# main.net
KiCad netlist of a schematic drawn in EAGLE
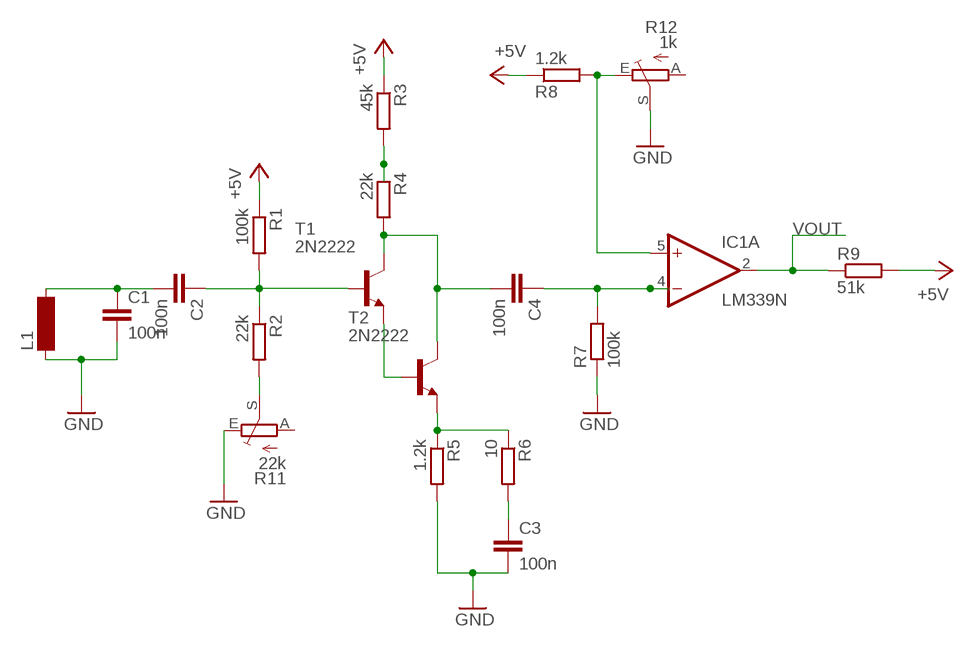
[diagram p0: schematic, sheet 1]

(export (version "E")
  (design (tool "Eeschema 10.0.6"))
  (components
    (comp (ref "C1")
      (value "100n")
      (footprint "eagle-import:C025-024X044")
      (libsource (lib "eagle-import") (part "C-EU025-024X044"))
    )
    (comp (ref "C2")
      (value "100n")
      (footprint "eagle-import:C025-024X044")
      (libsource (lib "eagle-import") (part "C-EU025-024X044"))
    )
    (comp (ref "C3")
      (value "100n")
      (footprint "eagle-import:C025-024X044")
      (libsource (lib "eagle-import") (part "C-EU025-024X044"))
    )
    (comp (ref "C4")
      (value "100n")
      (footprint "eagle-import:C025-024X044")
      (libsource (lib "eagle-import") (part "C-EU025-024X044"))
    )
    (comp (ref "IC1")
      (value "LM339N")
      (footprint "eagle-import:DIL14")
      (libsource (lib "eagle-import") (part "LM339N"))
    )
    (comp (ref "L1")
      (value "BS11")
      (footprint "eagle-import:BS11")
      (libsource (lib "eagle-import") (part "BS11"))
    )
    (comp (ref "R1")
      (value "100k")
      (footprint "eagle-import:0204V")
      (libsource (lib "eagle-import") (part "R-EU_0204/2V"))
    )
    (comp (ref "R2")
      (value "22k")
      (footprint "eagle-import:0204V")
      (libsource (lib "eagle-import") (part "R-EU_0204/2V"))
    )
    (comp (ref "R3")
      (value "45k")
      (footprint "eagle-import:0204V")
      (libsource (lib "eagle-import") (part "R-EU_0204/2V"))
    )
    (comp (ref "R4")
      (value "22k")
      (footprint "eagle-import:0204V")
      (libsource (lib "eagle-import") (part "R-EU_0204/2V"))
    )
    (comp (ref "R5")
      (value "1.2k")
      (footprint "eagle-import:0204V")
      (libsource (lib "eagle-import") (part "R-EU_0204/2V"))
    )
    (comp (ref "R6")
      (value "10")
      (footprint "eagle-import:0204V")
      (libsource (lib "eagle-import") (part "R-EU_0204/2V"))
    )
    (comp (ref "R7")
      (value "100k")
      (footprint "eagle-import:0204V")
      (libsource (lib "eagle-import") (part "R-EU_0204/2V"))
    )
    (comp (ref "R8")
      (value "1.2k")
      (footprint "eagle-import:0204V")
      (libsource (lib "eagle-import") (part "R-EU_0204/2V"))
    )
    (comp (ref "R9")
      (value "51k")
      (footprint "eagle-import:0204V")
      (libsource (lib "eagle-import") (part "R-EU_0204/2V"))
    )
    (comp (ref "R11")
      (value "22k")
      (footprint "eagle-import:B25P")
      (libsource (lib "eagle-import") (part "TRIM_EU-B25P"))
    )
    (comp (ref "R12")
      (value "1k")
      (footprint "eagle-import:B25P")
      (libsource (lib "eagle-import") (part "TRIM_EU-B25P"))
    )
    (comp (ref "T1")
      (value "2N2222")
      (footprint "eagle-import:TO18")
      (libsource (lib "eagle-import") (part "2N2222"))
    )
    (comp (ref "T2")
      (value "2N2222")
      (footprint "eagle-import:TO18")
      (libsource (lib "eagle-import") (part "2N2222"))
    )
  )
  (nets
    (net (code "1") (name "+5V") (class "Default")
      (node (ref "R1") (pin "1") (pinfunction "1_1") (pintype "passive"))
      (node (ref "R3") (pin "1") (pinfunction "1_1") (pintype "passive"))
      (node (ref "R8") (pin "1") (pinfunction "1_1") (pintype "passive"))
      (node (ref "R9") (pin "2") (pinfunction "2_2") (pintype "passive"))
    )
    (net (code "2") (name "/VOUT") (class "Default")
      (node (ref "IC1") (pin "2") (pinfunction "OUT_2") (pintype "open_collector"))
      (node (ref "R9") (pin "1") (pinfunction "1_1") (pintype "passive"))
    )
    (net (code "3") (name "GND") (class "Default")
      (node (ref "C1") (pin "2") (pinfunction "2_2") (pintype "passive"))
      (node (ref "C3") (pin "2") (pinfunction "2_2") (pintype "passive"))
      (node (ref "L1") (pin "1") (pinfunction "1_1") (pintype "passive"))
      (node (ref "R11") (pin "E") (pinfunction "E_E") (pintype "passive"))
      (node (ref "R12") (pin "S") (pinfunction "S_S") (pintype "passive"))
      (node (ref "R5") (pin "2") (pinfunction "2_2") (pintype "passive"))
      (node (ref "R7") (pin "1") (pinfunction "1_1") (pintype "passive"))
    )
    (net (code "4") (name "Net-(C1-Pad1)") (class "Default")
      (node (ref "C1") (pin "1") (pinfunction "1_1") (pintype "passive"))
      (node (ref "C2") (pin "2") (pinfunction "2_2") (pintype "passive"))
      (node (ref "L1") (pin "2") (pinfunction "2_2") (pintype "passive"))
    )
    (net (code "5") (name "Net-(C3-Pad1)") (class "Default")
      (node (ref "C3") (pin "1") (pinfunction "1_1") (pintype "passive"))
      (node (ref "R6") (pin "2") (pinfunction "2_2") (pintype "passive"))
    )
    (net (code "6") (name "Net-(IC1A-+IN)") (class "Default")
      (node (ref "IC1") (pin "5") (pinfunction "+IN_5") (pintype "input"))
      (node (ref "R12") (pin "E") (pinfunction "E_E") (pintype "passive"))
      (node (ref "R8") (pin "2") (pinfunction "2_2") (pintype "passive"))
    )
    (net (code "7") (name "Net-(IC1A--IN)") (class "Default")
      (node (ref "C4") (pin "1") (pinfunction "1_1") (pintype "passive"))
      (node (ref "IC1") (pin "4") (pinfunction "-IN_4") (pintype "input"))
      (node (ref "R7") (pin "2") (pinfunction "2_2") (pintype "passive"))
    )
    (net (code "8") (name "Net-(R3-Pad2)") (class "Default")
      (node (ref "R3") (pin "2") (pinfunction "2_2") (pintype "passive"))
      (node (ref "R4") (pin "1") (pinfunction "1_1") (pintype "passive"))
    )
    (net (code "9") (name "Net-(R11-PadS)") (class "Default")
      (node (ref "R11") (pin "S") (pinfunction "S_S") (pintype "passive"))
      (node (ref "R2") (pin "2") (pinfunction "2_2") (pintype "passive"))
    )
    (net (code "10") (name "Net-(T1-B)") (class "Default")
      (node (ref "C2") (pin "1") (pinfunction "1_1") (pintype "passive"))
      (node (ref "R1") (pin "2") (pinfunction "2_2") (pintype "passive"))
      (node (ref "R2") (pin "1") (pinfunction "1_1") (pintype "passive"))
      (node (ref "T1") (pin "2") (pinfunction "B_2") (pintype "passive"))
    )
    (net (code "11") (name "Net-(T1-C)") (class "Default")
      (node (ref "C4") (pin "2") (pinfunction "2_2") (pintype "passive"))
      (node (ref "R4") (pin "2") (pinfunction "2_2") (pintype "passive"))
      (node (ref "T1") (pin "3") (pinfunction "C_3") (pintype "passive"))
      (node (ref "T2") (pin "3") (pinfunction "C_3") (pintype "passive"))
    )
    (net (code "12") (name "Net-(T1-E)") (class "Default")
      (node (ref "T1") (pin "1") (pinfunction "E_1") (pintype "passive"))
      (node (ref "T2") (pin "2") (pinfunction "B_2") (pintype "passive"))
    )
    (net (code "13") (name "Net-(T2-E)") (class "Default")
      (node (ref "R5") (pin "1") (pinfunction "1_1") (pintype "passive"))
      (node (ref "R6") (pin "1") (pinfunction "1_1") (pintype "passive"))
      (node (ref "T2") (pin "1") (pinfunction "E_1") (pintype "passive"))
    )
    (net (code "14") (name "unconnected-(R11-PadA)") (class "Default")
      (node (ref "R11") (pin "A") (pinfunction "A_A") (pintype "passive"))
    )
    (net (code "15") (name "unconnected-(R12-PadA)") (class "Default")
      (node (ref "R12") (pin "A") (pinfunction "A_A") (pintype "passive"))
    )
  )
)
